# GSB-S05-V00-PSU5V.net
KiCad netlist of a schematic drawn in Altium Designer
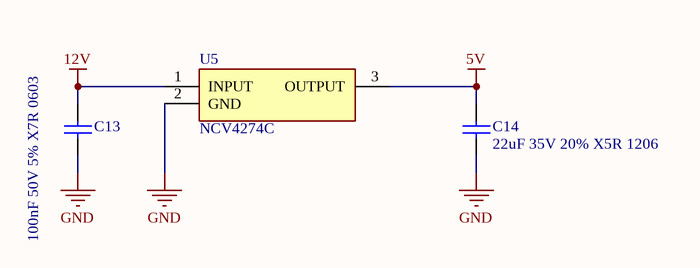
[diagram p0: GSB-S05-V00-PSU5V.SchDoc]

(export (version "E")
  (design (tool "Eeschema 10.0.6"))
  (components
    (comp (ref "C13")
      (value "100nF 50V 5% X7R 0603")
      (footprint "Cap_Ceramic_0603")
      (description "Capacitor, Ceramic, SMD, 100nF, 50V, 5%, X7R, 0603")
      (libsource (lib "StandardCapacitors") (part "100nF 50V 5% X7R 0603"))
    )
    (comp (ref "C14")
      (value "22uF 35V 20% X5R 1206")
      (footprint "Cap_Ceramic_1206")
      (description "22µF ±20% 35V Ceramic Capacitor X5R 1206 (3216 Metric)")
      (libsource (lib "StandardCapacitors") (part "22uF 35V 20% X5R 1206"))
    )
    (comp (ref "U5")
      (value "NCV4274C")
      (footprint "NCV4274CDT50RKG")
      (description "Integrated Circuit")
      (fields
        (field (name "MANUFACTURER_PART_NUMBER") "NCV4274CDT50RKG")
        (field (name "MOUSER PART NUMBER") "863-NCV4274CDT50RKG")
      )
      (libsource (lib "NCV4274CDT50RKG") (part "NCV4274C"))
    )
  )
  (nets
    (net (code "1") (name "5V") (class "Default")
      (node (ref "C14") (pin "2") (pinfunction "2_2") (pintype "passive"))
      (node (ref "U5") (pin "3") (pinfunction "OUTPUT_3") (pintype "passive"))
    )
    (net (code "2") (name "12V") (class "Default")
      (node (ref "C13") (pin "2") (pinfunction "2_2") (pintype "passive"))
      (node (ref "U5") (pin "1") (pinfunction "INPUT_1") (pintype "passive"))
    )
    (net (code "3") (name "GND") (class "Default")
      (node (ref "C13") (pin "1") (pinfunction "1_1") (pintype "passive"))
      (node (ref "C14") (pin "1") (pinfunction "1_1") (pintype "passive"))
      (node (ref "U5") (pin "2") (pinfunction "GND_2") (pintype "passive"))
    )
  )
)
